# SOIC28.net
KiCad netlist of a schematic drawn in Altium Designer
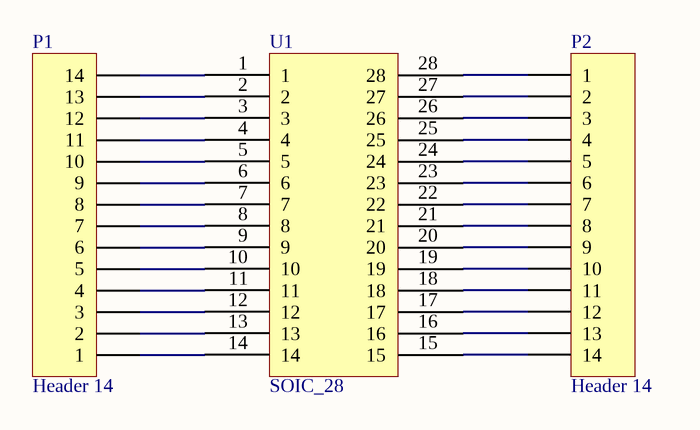
[diagram p0: SOIC28.SchDoc]

(export (version "E")
  (design (tool "Eeschema 10.0.6"))
  (components
    (comp (ref "P1")
      (value "Header 14")
      (footprint "HDR1X14")
      (description "Header, 14-Pin")
      (fields (field (name "PUBLISHER") "Altium Limited"))
      (libsource (lib "") (part "Header 14_1"))
    )
    (comp (ref "P2")
      (value "Header 14")
      (footprint "HDR1X14")
      (description "Header, 14-Pin")
      (fields (field (name "PUBLISHER") "Altium Limited"))
      (libsource (lib "Miscellaneous Connectors") (part "Header 14"))
    )
    (comp (ref "U1")
      (value "SOIC_28")
      (footprint "SOIC28")
      (libsource (lib "PCB_Breakout_Boards") (part "SOIC_28"))
    )
  )
  (nets
    (net (code "1") (name "Net-(P1-Pad1)") (class "Default")
      (node (ref "P1") (pin "1") (pinfunction "1_1") (pintype "passive"))
      (node (ref "U1") (pin "14") (pinfunction "14_14") (pintype "passive"))
    )
    (net (code "2") (name "Net-(P1-Pad2)") (class "Default")
      (node (ref "P1") (pin "2") (pinfunction "2_2") (pintype "passive"))
      (node (ref "U1") (pin "13") (pinfunction "13_13") (pintype "passive"))
    )
    (net (code "3") (name "Net-(P1-Pad3)") (class "Default")
      (node (ref "P1") (pin "3") (pinfunction "3_3") (pintype "passive"))
      (node (ref "U1") (pin "12") (pinfunction "12_12") (pintype "passive"))
    )
    (net (code "4") (name "Net-(P1-Pad4)") (class "Default")
      (node (ref "P1") (pin "4") (pinfunction "4_4") (pintype "passive"))
      (node (ref "U1") (pin "11") (pinfunction "11_11") (pintype "passive"))
    )
    (net (code "5") (name "Net-(P1-Pad5)") (class "Default")
      (node (ref "P1") (pin "5") (pinfunction "5_5") (pintype "passive"))
      (node (ref "U1") (pin "10") (pinfunction "10_10") (pintype "passive"))
    )
    (net (code "6") (name "Net-(P1-Pad6)") (class "Default")
      (node (ref "P1") (pin "6") (pinfunction "6_6") (pintype "passive"))
      (node (ref "U1") (pin "9") (pinfunction "9_9") (pintype "passive"))
    )
    (net (code "7") (name "Net-(P1-Pad7)") (class "Default")
      (node (ref "P1") (pin "7") (pinfunction "7_7") (pintype "passive"))
      (node (ref "U1") (pin "8") (pinfunction "8_8") (pintype "passive"))
    )
    (net (code "8") (name "Net-(P1-Pad8)") (class "Default")
      (node (ref "P1") (pin "8") (pinfunction "8_8") (pintype "passive"))
      (node (ref "U1") (pin "7") (pinfunction "7_7") (pintype "passive"))
    )
    (net (code "9") (name "Net-(P1-Pad9)") (class "Default")
      (node (ref "P1") (pin "9") (pinfunction "9_9") (pintype "passive"))
      (node (ref "U1") (pin "6") (pinfunction "6_6") (pintype "passive"))
    )
    (net (code "10") (name "Net-(P1-Pad10)") (class "Default")
      (node (ref "P1") (pin "10") (pinfunction "10_10") (pintype "passive"))
      (node (ref "U1") (pin "5") (pinfunction "5_5") (pintype "passive"))
    )
    (net (code "11") (name "Net-(P1-Pad11)") (class "Default")
      (node (ref "P1") (pin "11") (pinfunction "11_11") (pintype "passive"))
      (node (ref "U1") (pin "4") (pinfunction "4_4") (pintype "passive"))
    )
    (net (code "12") (name "Net-(P1-Pad12)") (class "Default")
      (node (ref "P1") (pin "12") (pinfunction "12_12") (pintype "passive"))
      (node (ref "U1") (pin "3") (pinfunction "3_3") (pintype "passive"))
    )
    (net (code "13") (name "Net-(P1-Pad13)") (class "Default")
      (node (ref "P1") (pin "13") (pinfunction "13_13") (pintype "passive"))
      (node (ref "U1") (pin "2") (pinfunction "2_2") (pintype "passive"))
    )
    (net (code "14") (name "Net-(P1-Pad14)") (class "Default")
      (node (ref "P1") (pin "14") (pinfunction "14_14") (pintype "passive"))
      (node (ref "U1") (pin "1") (pinfunction "1_1") (pintype "passive"))
    )
    (net (code "15") (name "Net-(P2-Pad1)") (class "Default")
      (node (ref "P2") (pin "1") (pinfunction "1_1") (pintype "passive"))
      (node (ref "U1") (pin "28") (pinfunction "28_28") (pintype "passive"))
    )
    (net (code "16") (name "Net-(P2-Pad2)") (class "Default")
      (node (ref "P2") (pin "2") (pinfunction "2_2") (pintype "passive"))
      (node (ref "U1") (pin "27") (pinfunction "27_27") (pintype "passive"))
    )
    (net (code "17") (name "Net-(P2-Pad3)") (class "Default")
      (node (ref "P2") (pin "3") (pinfunction "3_3") (pintype "passive"))
      (node (ref "U1") (pin "26") (pinfunction "26_26") (pintype "passive"))
    )
    (net (code "18") (name "Net-(P2-Pad4)") (class "Default")
      (node (ref "P2") (pin "4") (pinfunction "4_4") (pintype "passive"))
      (node (ref "U1") (pin "25") (pinfunction "25_25") (pintype "passive"))
    )
    (net (code "19") (name "Net-(P2-Pad5)") (class "Default")
      (node (ref "P2") (pin "5") (pinfunction "5_5") (pintype "passive"))
      (node (ref "U1") (pin "24") (pinfunction "24_24") (pintype "passive"))
    )
    (net (code "20") (name "Net-(P2-Pad6)") (class "Default")
      (node (ref "P2") (pin "6") (pinfunction "6_6") (pintype "passive"))
      (node (ref "U1") (pin "23") (pinfunction "23_23") (pintype "passive"))
    )
    (net (code "21") (name "Net-(P2-Pad7)") (class "Default")
      (node (ref "P2") (pin "7") (pinfunction "7_7") (pintype "passive"))
      (node (ref "U1") (pin "22") (pinfunction "22_22") (pintype "passive"))
    )
    (net (code "22") (name "Net-(P2-Pad8)") (class "Default")
      (node (ref "P2") (pin "8") (pinfunction "8_8") (pintype "passive"))
      (node (ref "U1") (pin "21") (pinfunction "21_21") (pintype "passive"))
    )
    (net (code "23") (name "Net-(P2-Pad9)") (class "Default")
      (node (ref "P2") (pin "9") (pinfunction "9_9") (pintype "passive"))
      (node (ref "U1") (pin "20") (pinfunction "20_20") (pintype "passive"))
    )
    (net (code "24") (name "Net-(P2-Pad10)") (class "Default")
      (node (ref "P2") (pin "10") (pinfunction "10_10") (pintype "passive"))
      (node (ref "U1") (pin "19") (pinfunction "19_19") (pintype "passive"))
    )
    (net (code "25") (name "Net-(P2-Pad11)") (class "Default")
      (node (ref "P2") (pin "11") (pinfunction "11_11") (pintype "passive"))
      (node (ref "U1") (pin "18") (pinfunction "18_18") (pintype "passive"))
    )
    (net (code "26") (name "Net-(P2-Pad12)") (class "Default")
      (node (ref "P2") (pin "12") (pinfunction "12_12") (pintype "passive"))
      (node (ref "U1") (pin "17") (pinfunction "17_17") (pintype "passive"))
    )
    (net (code "27") (name "Net-(P2-Pad13)") (class "Default")
      (node (ref "P2") (pin "13") (pinfunction "13_13") (pintype "passive"))
      (node (ref "U1") (pin "16") (pinfunction "16_16") (pintype "passive"))
    )
    (net (code "28") (name "Net-(P2-Pad14)") (class "Default")
      (node (ref "P2") (pin "14") (pinfunction "14_14") (pintype "passive"))
      (node (ref "U1") (pin "15") (pinfunction "15_15") (pintype "passive"))
    )
  )
)
